# IRDistroBoard.net
KiCad netlist of a schematic drawn in EAGLE
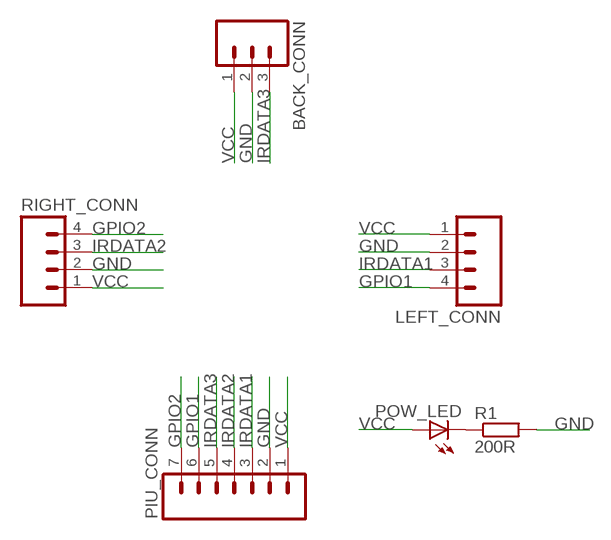
[diagram p0: schematic, sheet 1]

(export (version "E")
  (design (tool "Eeschema 10.0.6"))
  (components
    (comp (ref "BACK_CONN")
      (value "M03PTH")
      (footprint "eagle-import:1X03")
      (libsource (lib "eagle-import") (part "M03PTH"))
    )
    (comp (ref "LEFT_CONN")
      (value "M04PTH")
      (footprint "eagle-import:1X04")
      (libsource (lib "eagle-import") (part "M04PTH"))
    )
    (comp (ref "PIU_CONN")
      (value "M07")
      (footprint "eagle-import:1X07")
      (libsource (lib "eagle-import") (part "M07"))
    )
    (comp (ref "POW_LED")
      (value "LEDCHIPLED_0805")
      (footprint "eagle-import:CHIPLED_0805")
      (libsource (lib "eagle-import") (part "LEDCHIPLED_0805"))
    )
    (comp (ref "R1")
      (value "200R")
      (footprint "eagle-import:R805")
      (libsource (lib "eagle-import") (part "RESISTOR-0805R805"))
    )
    (comp (ref "RIGHT_CONN")
      (value "M04PTH")
      (footprint "eagle-import:1X04")
      (libsource (lib "eagle-import") (part "M04PTH"))
    )
  )
  (nets
    (net (code "1") (name "/GND") (class "Default")
      (node (ref "BACK_CONN") (pin "2") (pinfunction "2_2") (pintype "passive"))
      (node (ref "LEFT_CONN") (pin "2") (pinfunction "2_2") (pintype "passive"))
      (node (ref "PIU_CONN") (pin "2") (pinfunction "2_2") (pintype "passive"))
      (node (ref "R1") (pin "2") (pinfunction "2_2") (pintype "passive"))
      (node (ref "RIGHT_CONN") (pin "2") (pinfunction "2_2") (pintype "passive"))
    )
    (net (code "2") (name "/GPIO1") (class "Default")
      (node (ref "LEFT_CONN") (pin "4") (pinfunction "4_4") (pintype "passive"))
      (node (ref "PIU_CONN") (pin "6") (pinfunction "6_6") (pintype "passive"))
    )
    (net (code "3") (name "/GPIO2") (class "Default")
      (node (ref "PIU_CONN") (pin "7") (pinfunction "7_7") (pintype "passive"))
      (node (ref "RIGHT_CONN") (pin "4") (pinfunction "4_4") (pintype "passive"))
    )
    (net (code "4") (name "/IRDATA1") (class "Default")
      (node (ref "LEFT_CONN") (pin "3") (pinfunction "3_3") (pintype "passive"))
      (node (ref "PIU_CONN") (pin "3") (pinfunction "3_3") (pintype "passive"))
    )
    (net (code "5") (name "/IRDATA2") (class "Default")
      (node (ref "PIU_CONN") (pin "4") (pinfunction "4_4") (pintype "passive"))
      (node (ref "RIGHT_CONN") (pin "3") (pinfunction "3_3") (pintype "passive"))
    )
    (net (code "6") (name "/IRDATA3") (class "Default")
      (node (ref "BACK_CONN") (pin "3") (pinfunction "3_3") (pintype "passive"))
      (node (ref "PIU_CONN") (pin "5") (pinfunction "5_5") (pintype "passive"))
    )
    (net (code "7") (name "/VCC") (class "Default")
      (node (ref "BACK_CONN") (pin "1") (pinfunction "1_1") (pintype "passive"))
      (node (ref "LEFT_CONN") (pin "1") (pinfunction "1_1") (pintype "passive"))
      (node (ref "PIU_CONN") (pin "1") (pinfunction "1_1") (pintype "passive"))
      (node (ref "POW_LED") (pin "A") (pinfunction "A_A") (pintype "passive"))
      (node (ref "RIGHT_CONN") (pin "1") (pinfunction "1_1") (pintype "passive"))
    )
    (net (code "8") (name "Net-(POW_LED-PadC)") (class "Default")
      (node (ref "POW_LED") (pin "C") (pinfunction "C_C") (pintype "passive"))
      (node (ref "R1") (pin "1") (pinfunction "1_1") (pintype "passive"))
    )
  )
)
